# SHC.net
KiCad netlist of a schematic drawn in EasyEDA
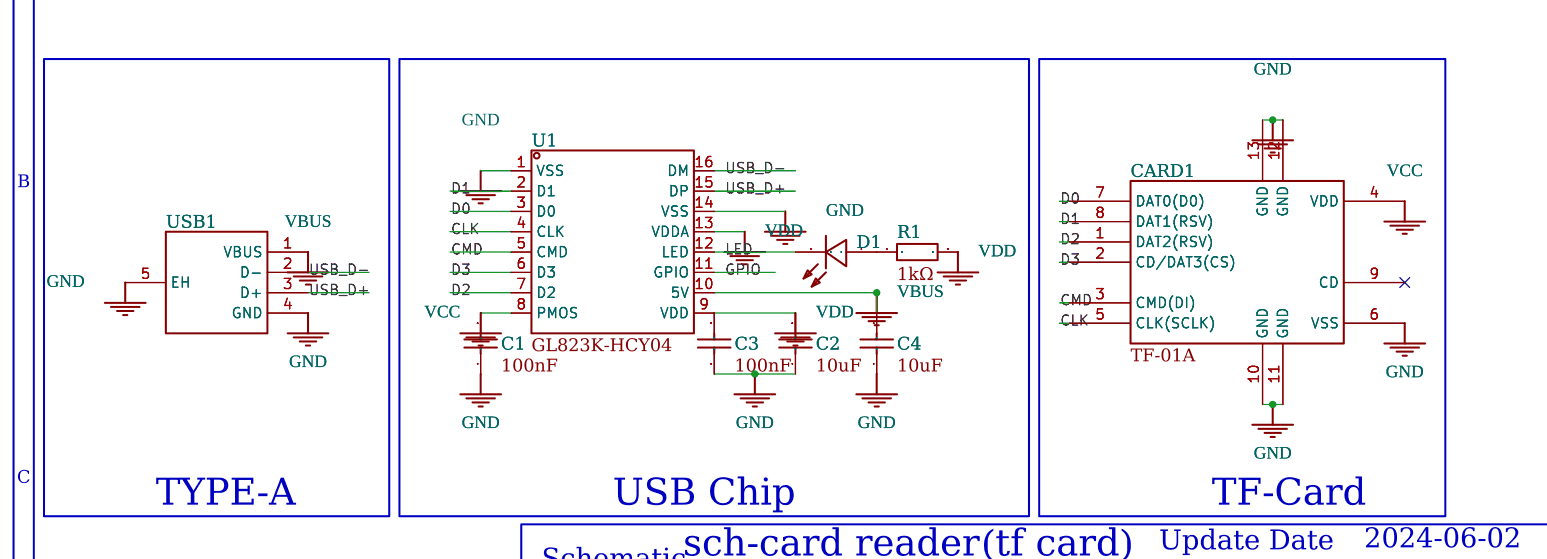
[diagram p0: schematic sheet]

(export (version "E")
  (design (tool "Eeschema 10.0.6"))
  (components
    (comp (ref "C1")
      (value "100nF")
      (fields
        (field (name "Manufacturer Part") "CL21B104KCFNNNE")
        (field (name "Manufacturer") "SAMSUNG(三星)")
      )
      (libsource (lib "") (part "Unknown_260_-310"))
    )
    (comp (ref "C2")
      (value "10uF")
      (fields
        (field (name "Manufacturer Part") "CL21A106KAYNNNE")
        (field (name "Manufacturer") "SAMSUNG(三星)")
      )
      (libsource (lib "") (part "Unknown_415_-310"))
    )
    (comp (ref "C3")
      (value "100nF")
      (fields
        (field (name "Manufacturer Part") "CL21B104KCFNNNE")
        (field (name "Manufacturer") "SAMSUNG(三星)")
      )
      (libsource (lib "") (part "Unknown_375_-310"))
    )
    (comp (ref "C4")
      (value "10uF")
      (fields
        (field (name "Manufacturer Part") "CL21A106KAYNNNE")
        (field (name "Manufacturer") "SAMSUNG(三星)")
      )
      (libsource (lib "") (part "Unknown_455_-310"))
    )
    (comp (ref "CARD1")
      (value "TF-01A")
      (fields (field (name "Manufacturer") "韩国韩荣"))
      (libsource (lib "") (part "Unknown_625_-350"))
    )
    (comp (ref "D1")
      (value "KT-0805翠绿")
      (fields (field (name "Manufacturer") "KENTO"))
      (libsource (lib "") (part "Unknown_435_-355"))
    )
    (comp (ref "R1")
      (value "1kΩ")
      (fields
        (field (name "Manufacturer Part") "0805W8F1001T5E")
        (field (name "Manufacturer") "UNI-ROYAL(厚声)")
      )
      (libsource (lib "") (part "Unknown_475_-355"))
    )
    (comp (ref "U1")
      (value "GL823K-HCY04")
      (fields (field (name "Manufacturer") "GENESYS(创惟)"))
      (libsource (lib "") (part "Unknown_325_-360"))
    )
    (comp (ref "USB1")
      (value "AM 180°")
      (fields (field (name "Manufacturer") "SHOU HAN(首韩)"))
      (libsource (lib "") (part "Unknown_130_-340"))
    )
  )
  (nets
    (net (code "1") (name "/CLK") (class "Default")
      (node (ref "CARD1") (pin "5") (pinfunction "CLK(SCLK)_5") (pintype "unspecified"))
      (node (ref "U1") (pin "4") (pinfunction "CLK_4") (pintype "unspecified"))
    )
    (net (code "2") (name "/CMD") (class "Default")
      (node (ref "CARD1") (pin "3") (pinfunction "CMD(DI)_3") (pintype "unspecified"))
      (node (ref "U1") (pin "5") (pinfunction "CMD_5") (pintype "unspecified"))
    )
    (net (code "3") (name "/D0") (class "Default")
      (node (ref "CARD1") (pin "7") (pinfunction "DAT0(D0)_7") (pintype "unspecified"))
      (node (ref "U1") (pin "3") (pinfunction "D0_3") (pintype "unspecified"))
    )
    (net (code "4") (name "/D1") (class "Default")
      (node (ref "CARD1") (pin "8") (pinfunction "DAT1(RSV)_8") (pintype "unspecified"))
      (node (ref "U1") (pin "2") (pinfunction "D1_2") (pintype "unspecified"))
    )
    (net (code "5") (name "/D2") (class "Default")
      (node (ref "CARD1") (pin "1") (pinfunction "DAT2(RSV)_1") (pintype "unspecified"))
      (node (ref "U1") (pin "7") (pinfunction "D2_7") (pintype "unspecified"))
    )
    (net (code "6") (name "/D3") (class "Default")
      (node (ref "CARD1") (pin "2") (pinfunction "CD/DAT3(CS)_2") (pintype "unspecified"))
      (node (ref "U1") (pin "6") (pinfunction "D3_6") (pintype "unspecified"))
    )
    (net (code "7") (name "/GPIO") (class "Default")
      (node (ref "U1") (pin "11") (pinfunction "GPIO_11") (pintype "unspecified"))
    )
    (net (code "8") (name "/LED") (class "Default")
      (node (ref "D1") (pin "2") (pinfunction "K_2") (pintype "unspecified"))
      (node (ref "U1") (pin "12") (pinfunction "LED_12") (pintype "unspecified"))
    )
    (net (code "9") (name "/USB_D+") (class "Default")
      (node (ref "U1") (pin "15") (pinfunction "DP_15") (pintype "unspecified"))
      (node (ref "USB1") (pin "3") (pinfunction "D+_3") (pintype "unspecified"))
    )
    (net (code "10") (name "/USB_D-") (class "Default")
      (node (ref "U1") (pin "16") (pinfunction "DM_16") (pintype "unspecified"))
      (node (ref "USB1") (pin "2") (pinfunction "D-_2") (pintype "unspecified"))
    )
    (net (code "11") (name "GND") (class "Default")
      (node (ref "C1") (pin "1") (pinfunction "1_1") (pintype "unspecified"))
      (node (ref "C2") (pin "1") (pinfunction "1_1") (pintype "unspecified"))
      (node (ref "C3") (pin "1") (pinfunction "1_1") (pintype "unspecified"))
      (node (ref "C4") (pin "1") (pinfunction "1_1") (pintype "unspecified"))
      (node (ref "CARD1") (pin "10") (pinfunction "GND_10") (pintype "unspecified"))
      (node (ref "CARD1") (pin "11") (pinfunction "GND_11") (pintype "unspecified"))
      (node (ref "CARD1") (pin "12") (pinfunction "GND_12") (pintype "unspecified"))
      (node (ref "CARD1") (pin "13") (pinfunction "GND_13") (pintype "unspecified"))
      (node (ref "CARD1") (pin "6") (pinfunction "VSS_6") (pintype "unspecified"))
      (node (ref "U1") (pin "1") (pinfunction "VSS_1") (pintype "unspecified"))
      (node (ref "U1") (pin "14") (pinfunction "VSS_14") (pintype "unspecified"))
      (node (ref "USB1") (pin "4") (pinfunction "GND_4") (pintype "unspecified"))
      (node (ref "USB1") (pin "5") (pinfunction "EH_5") (pintype "unspecified"))
    )
    (net (code "12") (name "Net-(D1-A)") (class "Default")
      (node (ref "D1") (pin "1") (pinfunction "A_1") (pintype "unspecified"))
      (node (ref "R1") (pin "1") (pinfunction "1_1") (pintype "unspecified"))
    )
    (net (code "13") (name "VBUS") (class "Default")
      (node (ref "C4") (pin "2") (pinfunction "2_2") (pintype "unspecified"))
      (node (ref "U1") (pin "10") (pinfunction "5V_10") (pintype "unspecified"))
      (node (ref "USB1") (pin "1") (pinfunction "VBUS_1") (pintype "unspecified"))
    )
    (net (code "14") (name "VCC") (class "Default")
      (node (ref "C1") (pin "2") (pinfunction "2_2") (pintype "unspecified"))
      (node (ref "CARD1") (pin "4") (pinfunction "VDD_4") (pintype "unspecified"))
      (node (ref "U1") (pin "8") (pinfunction "PMOS_8") (pintype "unspecified"))
    )
    (net (code "15") (name "VDD") (class "Default")
      (node (ref "C2") (pin "2") (pinfunction "2_2") (pintype "unspecified"))
      (node (ref "C3") (pin "2") (pinfunction "2_2") (pintype "unspecified"))
      (node (ref "R1") (pin "2") (pinfunction "2_2") (pintype "unspecified"))
      (node (ref "U1") (pin "13") (pinfunction "VDDA_13") (pintype "unspecified"))
      (node (ref "U1") (pin "9") (pinfunction "VDD_9") (pintype "unspecified"))
    )
    (net (code "16") (name "unconnected-(CARD1-CD-Pad9)") (class "Default")
      (node (ref "CARD1") (pin "9") (pinfunction "CD_9") (pintype "unspecified+no_connect"))
    )
  )
)
